# max232.net
KiCad netlist of a schematic drawn in EAGLE
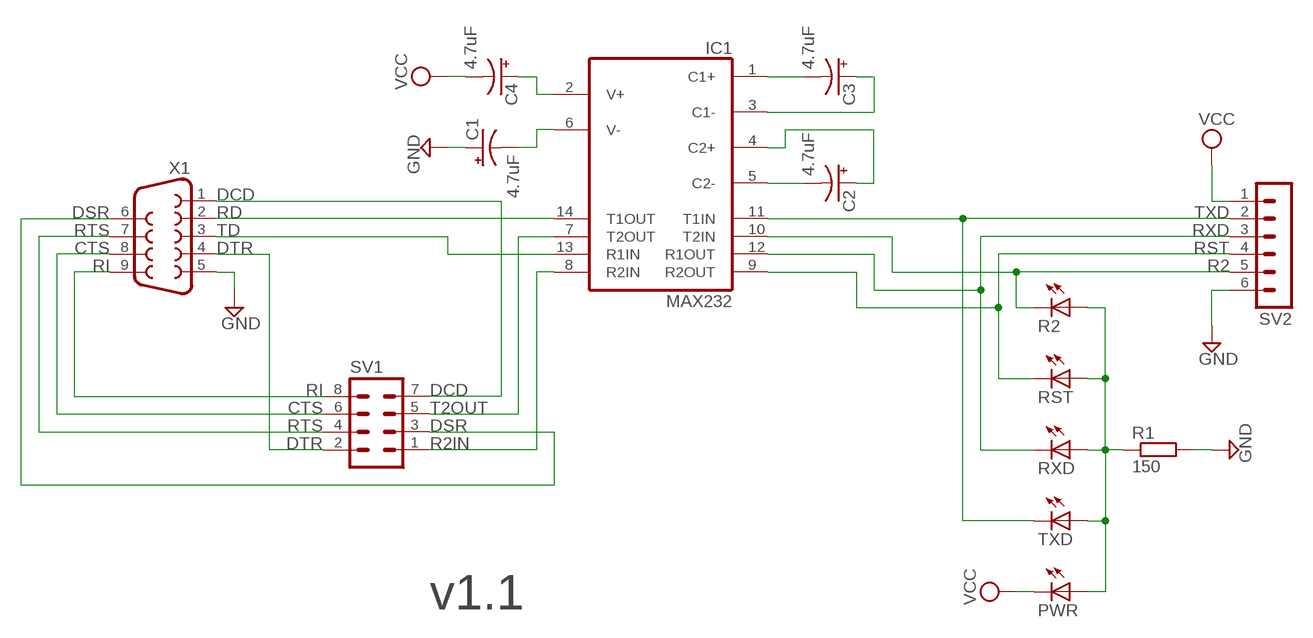
[diagram p0: schematic, sheet 1]

(export (version "E")
  (design (tool "Eeschema 10.0.6"))
  (components
    (comp (ref "C1")
      (value "4.7uF")
      (footprint "eagle-import:E2-4")
      (libsource (lib "eagle-import") (part "CPOL-USE2-4"))
    )
    (comp (ref "C2")
      (value "4.7uF")
      (footprint "eagle-import:E2-4")
      (libsource (lib "eagle-import") (part "CPOL-USE2-4"))
    )
    (comp (ref "C3")
      (value "4.7uF")
      (footprint "eagle-import:E2-4")
      (libsource (lib "eagle-import") (part "CPOL-USE2-4"))
    )
    (comp (ref "C4")
      (value "4.7uF")
      (footprint "eagle-import:E2-4")
      (libsource (lib "eagle-import") (part "CPOL-USE2-4"))
    )
    (comp (ref "IC1")
      (value "MAX232")
      (footprint "eagle-import:DIL16")
      (fields (field (name "MF") "MAXIM") (field (name "MPN") "MAX232ACPE+"))
      (libsource (lib "eagle-import") (part "MAX232"))
    )
    (comp (ref "PWR")
      (value "LED3MM")
      (footprint "eagle-import:LED3MM")
      (libsource (lib "eagle-import") (part "LED3MM"))
    )
    (comp (ref "R1")
      (value "150")
      (footprint "eagle-import:0207_10")
      (libsource (lib "eagle-import") (part "R-EU_0207/10"))
    )
    (comp (ref "R2")
      (value "LED3MM")
      (footprint "eagle-import:LED3MM")
      (libsource (lib "eagle-import") (part "LED3MM"))
    )
    (comp (ref "RST")
      (value "LED3MM")
      (footprint "eagle-import:LED3MM")
      (libsource (lib "eagle-import") (part "LED3MM"))
    )
    (comp (ref "RXD")
      (value "LED3MM")
      (footprint "eagle-import:LED3MM")
      (libsource (lib "eagle-import") (part "LED3MM"))
    )
    (comp (ref "SV1")
      (value "MA04-2")
      (footprint "eagle-import:MA04-2")
      (libsource (lib "eagle-import") (part "MA04-2"))
    )
    (comp (ref "SV2")
      (value "MA06-1")
      (footprint "eagle-import:MA06-1")
      (libsource (lib "eagle-import") (part "MA06-1"))
    )
    (comp (ref "TXD")
      (value "LED3MM")
      (footprint "eagle-import:LED3MM")
      (libsource (lib "eagle-import") (part "LED3MM"))
    )
    (comp (ref "X1")
      (value "F09HP")
      (footprint "eagle-import:F09HP")
      (libsource (lib "eagle-import") (part "F09HP"))
    )
  )
  (nets
    (net (code "1") (name "/CTS") (class "Default")
      (node (ref "SV1") (pin "6") (pinfunction "6_6") (pintype "passive"))
      (node (ref "X1") (pin "8") (pinfunction "8_8") (pintype "passive"))
    )
    (net (code "2") (name "/DCD") (class "Default")
      (node (ref "SV1") (pin "7") (pinfunction "7_7") (pintype "passive"))
      (node (ref "X1") (pin "1") (pinfunction "1_1") (pintype "passive"))
    )
    (net (code "3") (name "/DSR") (class "Default")
      (node (ref "SV1") (pin "3") (pinfunction "3_3") (pintype "passive"))
      (node (ref "X1") (pin "6") (pinfunction "6_6") (pintype "passive"))
    )
    (net (code "4") (name "/DTR") (class "Default")
      (node (ref "SV1") (pin "2") (pinfunction "2_2") (pintype "passive"))
      (node (ref "X1") (pin "4") (pinfunction "4_4") (pintype "passive"))
    )
    (net (code "5") (name "/RD") (class "Default")
      (node (ref "IC1") (pin "14") (pinfunction "T1OUT_14") (pintype "output"))
      (node (ref "X1") (pin "2") (pinfunction "2_2") (pintype "passive"))
    )
    (net (code "6") (name "/RI") (class "Default")
      (node (ref "SV1") (pin "8") (pinfunction "8_8") (pintype "passive"))
      (node (ref "X1") (pin "9") (pinfunction "9_9") (pintype "passive"))
    )
    (net (code "7") (name "/RTS") (class "Default")
      (node (ref "SV1") (pin "4") (pinfunction "4_4") (pintype "passive"))
      (node (ref "X1") (pin "7") (pinfunction "7_7") (pintype "passive"))
    )
    (net (code "8") (name "/TD") (class "Default")
      (node (ref "IC1") (pin "13") (pinfunction "R1IN_13") (pintype "input"))
      (node (ref "X1") (pin "3") (pinfunction "3_3") (pintype "passive"))
    )
    (net (code "9") (name "GND") (class "Default")
      (node (ref "C1") (pin "+") (pinfunction "+_+") (pintype "passive"))
      (node (ref "R1") (pin "2") (pinfunction "2_2") (pintype "passive"))
      (node (ref "SV2") (pin "6") (pinfunction "6_6") (pintype "passive"))
      (node (ref "X1") (pin "5") (pinfunction "5_5") (pintype "passive"))
    )
    (net (code "10") (name "Net-(IC1A-C1+)") (class "Default")
      (node (ref "C3") (pin "-") (pinfunction "-_-") (pintype "passive"))
      (node (ref "IC1") (pin "1") (pinfunction "C1+_1") (pintype "bidirectional"))
    )
    (net (code "11") (name "Net-(IC1A-C1-)") (class "Default")
      (node (ref "C3") (pin "+") (pinfunction "+_+") (pintype "passive"))
      (node (ref "IC1") (pin "3") (pinfunction "C1-_3") (pintype "bidirectional"))
    )
    (net (code "12") (name "Net-(IC1A-C2+)") (class "Default")
      (node (ref "C2") (pin "+") (pinfunction "+_+") (pintype "passive"))
      (node (ref "IC1") (pin "4") (pinfunction "C2+_4") (pintype "bidirectional"))
    )
    (net (code "13") (name "Net-(IC1A-C2-)") (class "Default")
      (node (ref "C2") (pin "-") (pinfunction "-_-") (pintype "passive"))
      (node (ref "IC1") (pin "5") (pinfunction "C2-_5") (pintype "bidirectional"))
    )
    (net (code "14") (name "Net-(IC1A-R1OUT)") (class "Default")
      (node (ref "IC1") (pin "12") (pinfunction "R1OUT_12") (pintype "output"))
      (node (ref "RXD") (pin "K") (pinfunction "C_K") (pintype "passive"))
      (node (ref "SV2") (pin "3") (pinfunction "3_3") (pintype "passive"))
    )
    (net (code "15") (name "Net-(IC1A-R2IN)") (class "Default")
      (node (ref "IC1") (pin "8") (pinfunction "R2IN_8") (pintype "input"))
      (node (ref "SV1") (pin "1") (pinfunction "1_1") (pintype "passive"))
    )
    (net (code "16") (name "Net-(IC1A-R2OUT)") (class "Default")
      (node (ref "IC1") (pin "9") (pinfunction "R2OUT_9") (pintype "output"))
      (node (ref "RST") (pin "K") (pinfunction "C_K") (pintype "passive"))
      (node (ref "SV2") (pin "4") (pinfunction "4_4") (pintype "passive"))
    )
    (net (code "17") (name "Net-(IC1A-T1IN)") (class "Default")
      (node (ref "IC1") (pin "11") (pinfunction "T1IN_11") (pintype "input"))
      (node (ref "SV2") (pin "2") (pinfunction "2_2") (pintype "passive"))
      (node (ref "TXD") (pin "K") (pinfunction "C_K") (pintype "passive"))
    )
    (net (code "18") (name "Net-(IC1A-T2IN)") (class "Default")
      (node (ref "IC1") (pin "10") (pinfunction "T2IN_10") (pintype "input"))
      (node (ref "R2") (pin "K") (pinfunction "C_K") (pintype "passive"))
      (node (ref "SV2") (pin "5") (pinfunction "5_5") (pintype "passive"))
    )
    (net (code "19") (name "Net-(IC1A-T2OUT)") (class "Default")
      (node (ref "IC1") (pin "7") (pinfunction "T2OUT_7") (pintype "output"))
      (node (ref "SV1") (pin "5") (pinfunction "5_5") (pintype "passive"))
    )
    (net (code "20") (name "Net-(IC1A-V+)") (class "Default")
      (node (ref "C4") (pin "+") (pinfunction "+_+") (pintype "passive"))
      (node (ref "IC1") (pin "2") (pinfunction "V+_2") (pintype "bidirectional"))
    )
    (net (code "21") (name "Net-(IC1A-V-)") (class "Default")
      (node (ref "C1") (pin "-") (pinfunction "-_-") (pintype "passive"))
      (node (ref "IC1") (pin "6") (pinfunction "V-_6") (pintype "bidirectional"))
    )
    (net (code "22") (name "Net-(PWR-PadA)") (class "Default")
      (node (ref "PWR") (pin "A") (pinfunction "A_A") (pintype "passive"))
      (node (ref "R1") (pin "1") (pinfunction "1_1") (pintype "passive"))
      (node (ref "R2") (pin "A") (pinfunction "A_A") (pintype "passive"))
      (node (ref "RST") (pin "A") (pinfunction "A_A") (pintype "passive"))
      (node (ref "RXD") (pin "A") (pinfunction "A_A") (pintype "passive"))
      (node (ref "TXD") (pin "A") (pinfunction "A_A") (pintype "passive"))
    )
    (net (code "23") (name "VCC") (class "Default")
      (node (ref "C4") (pin "-") (pinfunction "-_-") (pintype "passive"))
      (node (ref "PWR") (pin "K") (pinfunction "C_K") (pintype "passive"))
      (node (ref "SV2") (pin "1") (pinfunction "1_1") (pintype "passive"))
    )
  )
)
